# mux_board_final_gp.net
KiCad netlist of a schematic drawn in EAGLE
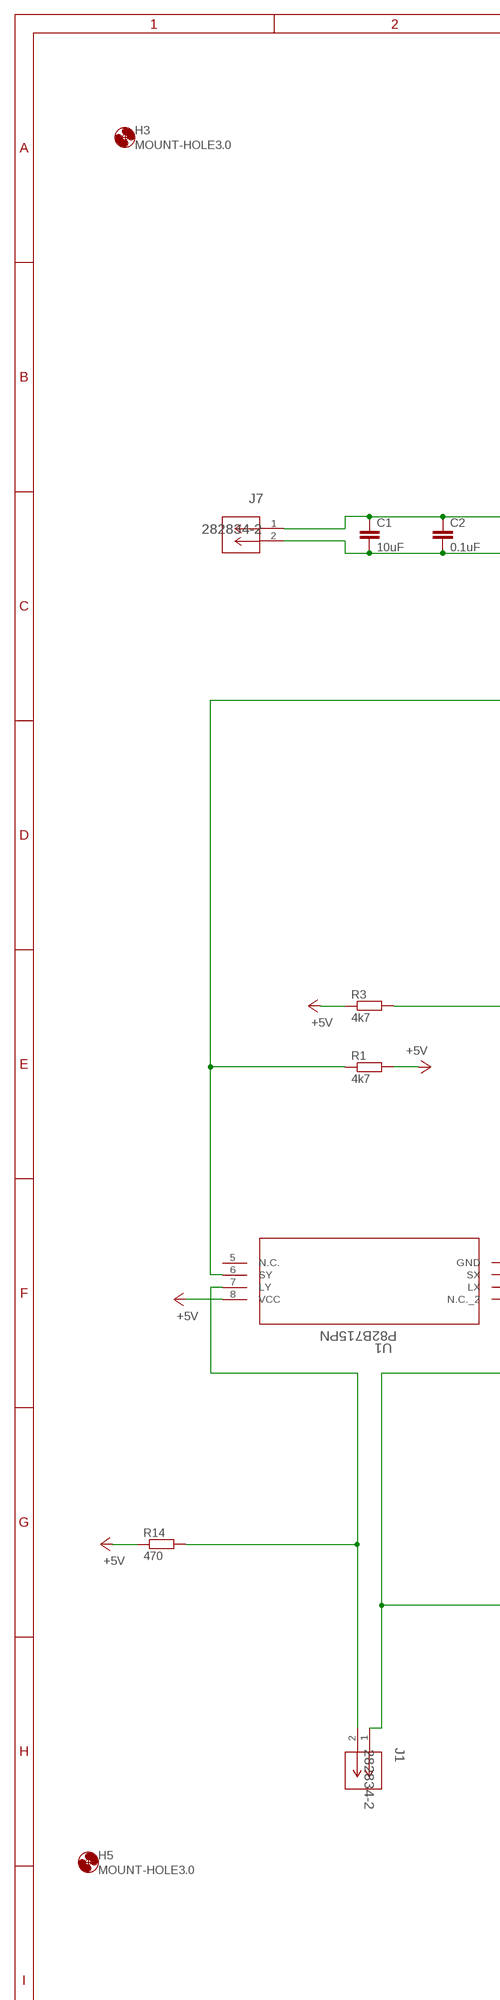
[diagram p0: schematic, sheet 1, part 1 of 2]
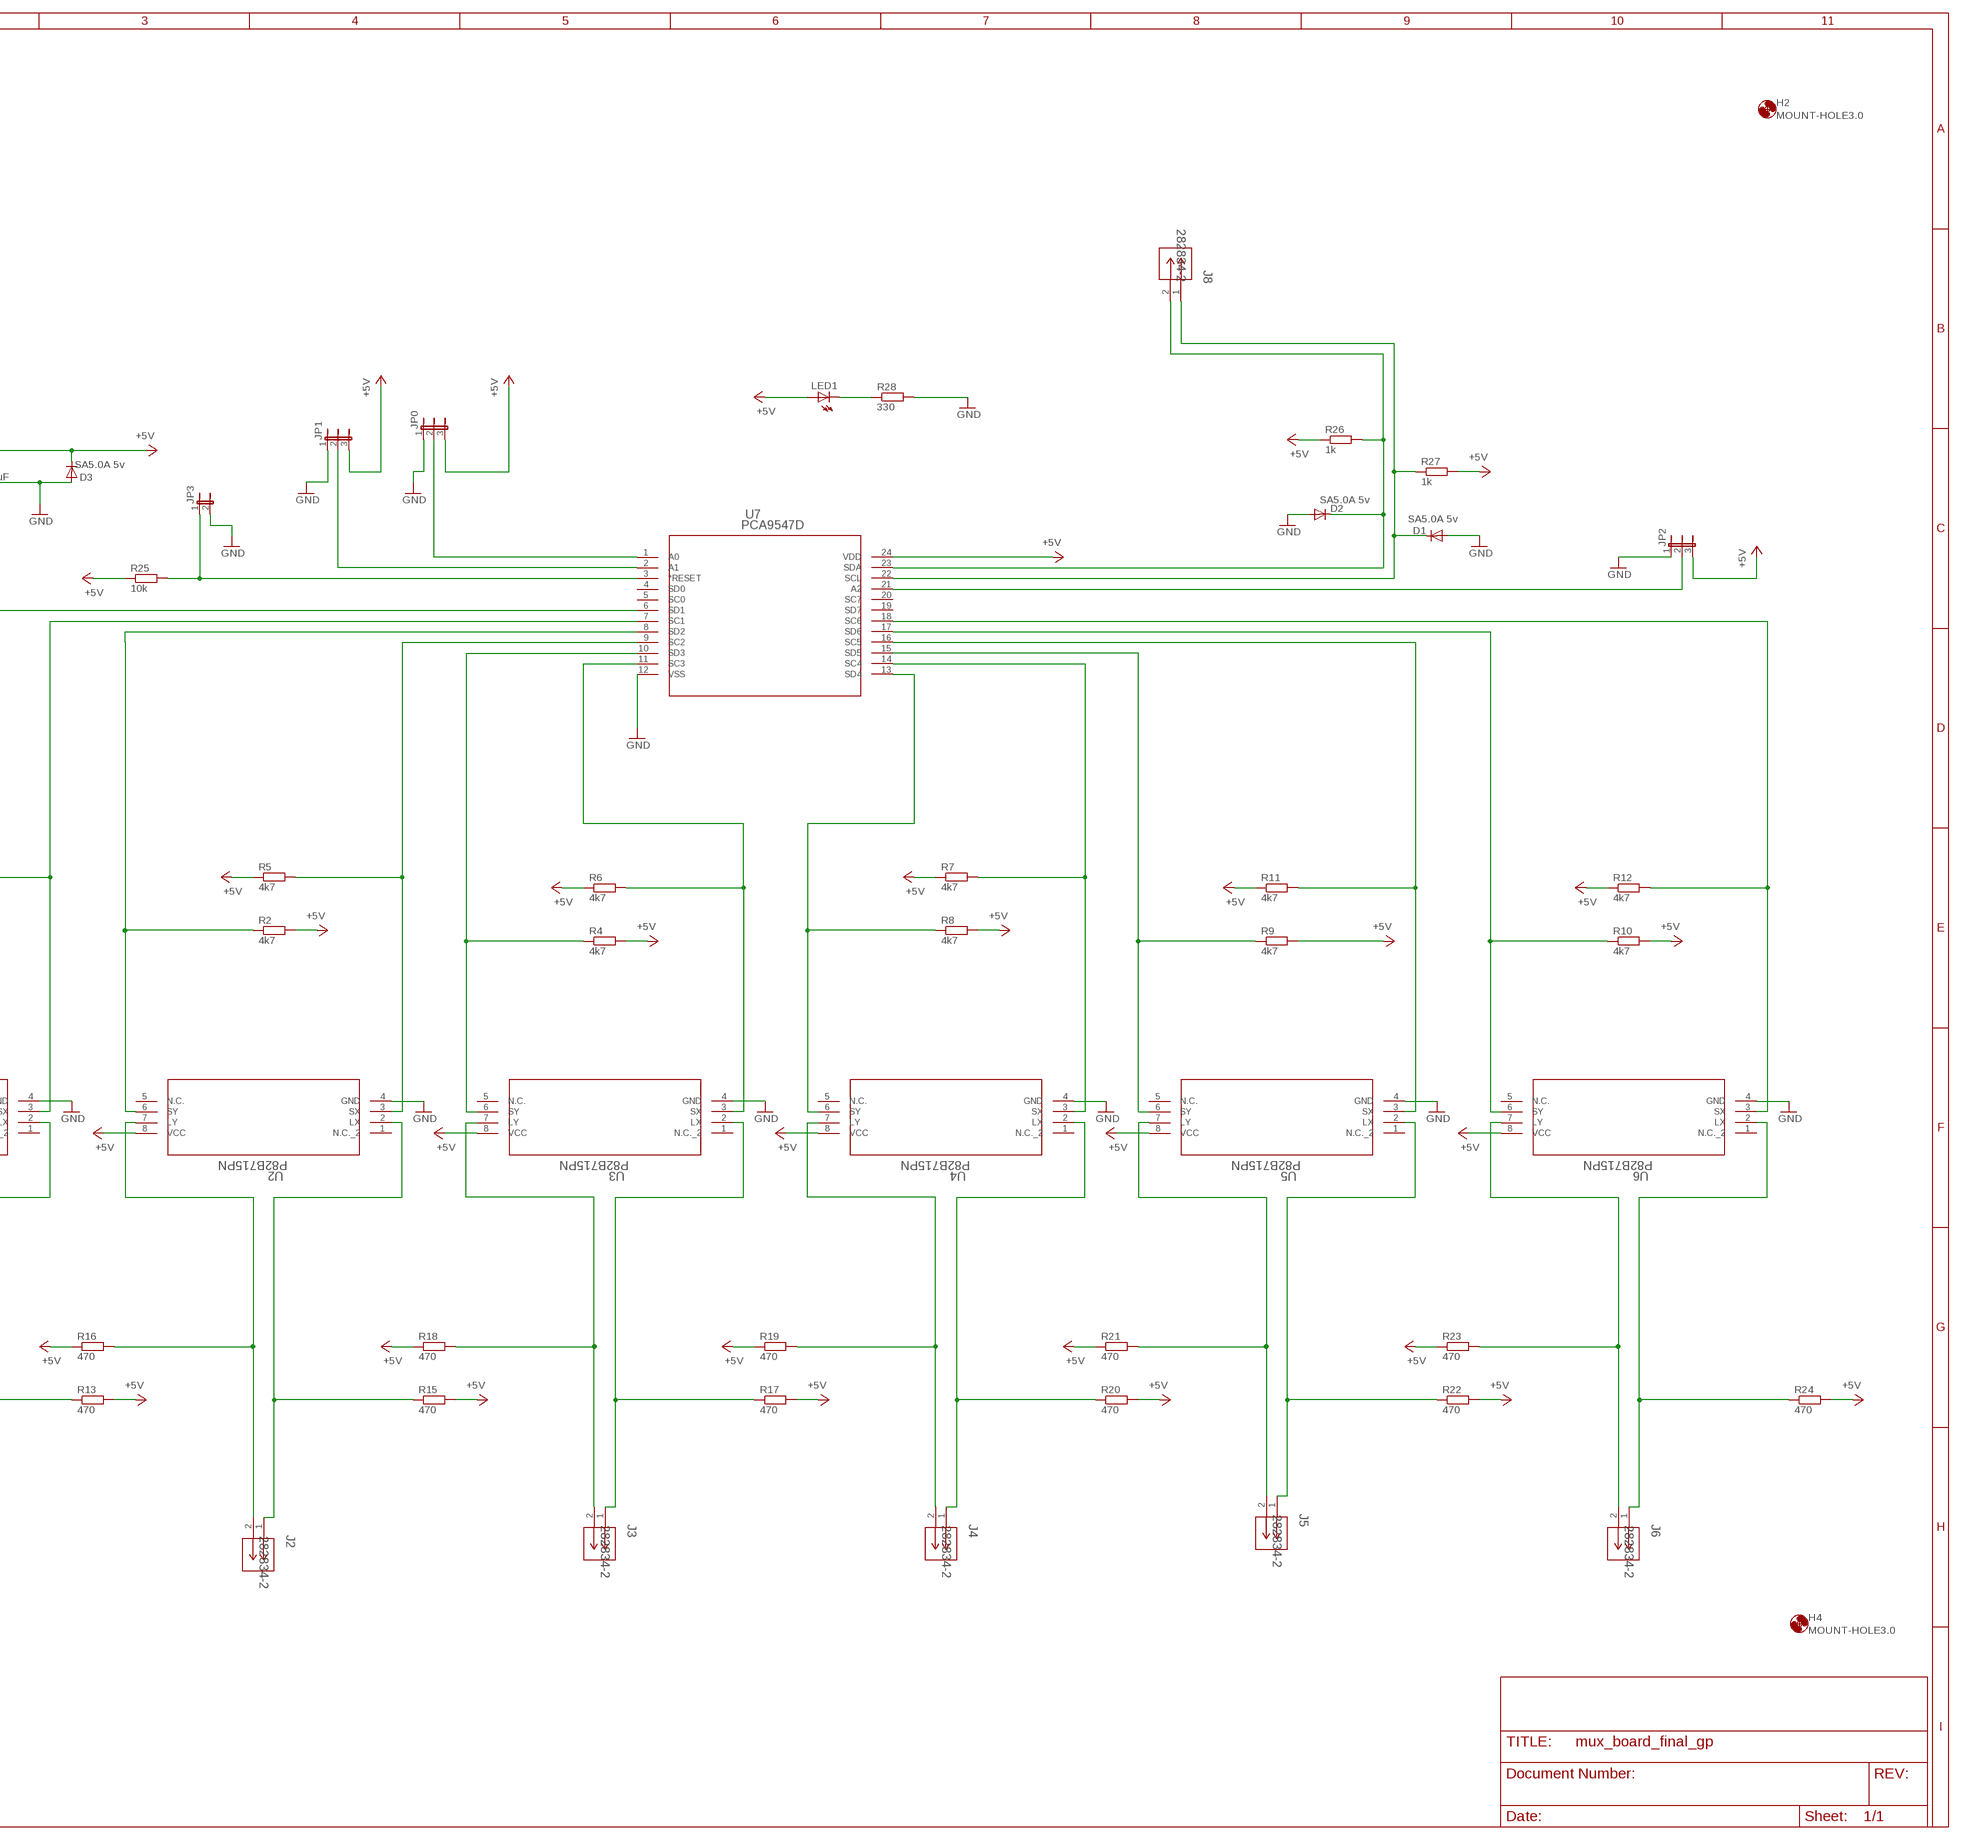
[diagram p1: schematic, sheet 1, part 2 of 2]

(export (version "E")
  (design (tool "Eeschema 10.0.6"))
  (components
    (comp (ref "C1")
      (value "10uF")
      (footprint "eagle-import:C025-025X050")
      (libsource (lib "eagle-import") (part "C-EU025-025X050"))
    )
    (comp (ref "C2")
      (value "0.1uF")
      (footprint "eagle-import:C025-025X050")
      (libsource (lib "eagle-import") (part "C-EU025-025X050"))
    )
    (comp (ref "D1")
      (value "SA5.0A 5v")
      (footprint "eagle-import:DO41-10")
      (libsource (lib "eagle-import") (part "1N4004"))
    )
    (comp (ref "D2")
      (value "SA5.0A 5v")
      (footprint "eagle-import:DO41-10")
      (libsource (lib "eagle-import") (part "1N4004"))
    )
    (comp (ref "D3")
      (value "SA5.0A 5v")
      (footprint "eagle-import:DO41-10")
      (libsource (lib "eagle-import") (part "1N4004"))
    )
    (comp (ref "H2")
      (value "MOUNT-HOLE3.0")
      (footprint "eagle-import:3,0")
      (libsource (lib "eagle-import") (part "MOUNT-HOLE3.0"))
    )
    (comp (ref "H3")
      (value "MOUNT-HOLE3.0")
      (footprint "eagle-import:3,0")
      (libsource (lib "eagle-import") (part "MOUNT-HOLE3.0"))
    )
    (comp (ref "H4")
      (value "MOUNT-HOLE3.0")
      (footprint "eagle-import:3,0")
      (libsource (lib "eagle-import") (part "MOUNT-HOLE3.0"))
    )
    (comp (ref "H5")
      (value "MOUNT-HOLE3.0")
      (footprint "eagle-import:3,0")
      (libsource (lib "eagle-import") (part "MOUNT-HOLE3.0"))
    )
    (comp (ref "J1")
      (value "282834-2")
      (footprint "eagle-import:CONN_282834-2")
      (fields (field (name "RSPARTNUMBER") "7100104"))
      (libsource (lib "eagle-import") (part "282834-2"))
    )
    (comp (ref "J2")
      (value "282834-2")
      (footprint "eagle-import:CONN_282834-2")
      (fields (field (name "RSPARTNUMBER") "7100104"))
      (libsource (lib "eagle-import") (part "282834-2"))
    )
    (comp (ref "J3")
      (value "282834-2")
      (footprint "eagle-import:CONN_282834-2")
      (fields (field (name "RSPARTNUMBER") "7100104"))
      (libsource (lib "eagle-import") (part "282834-2"))
    )
    (comp (ref "J4")
      (value "282834-2")
      (footprint "eagle-import:CONN_282834-2")
      (fields (field (name "RSPARTNUMBER") "7100104"))
      (libsource (lib "eagle-import") (part "282834-2"))
    )
    (comp (ref "J5")
      (value "282834-2")
      (footprint "eagle-import:CONN_282834-2")
      (fields (field (name "RSPARTNUMBER") "7100104"))
      (libsource (lib "eagle-import") (part "282834-2"))
    )
    (comp (ref "J6")
      (value "282834-2")
      (footprint "eagle-import:CONN_282834-2")
      (fields (field (name "RSPARTNUMBER") "7100104"))
      (libsource (lib "eagle-import") (part "282834-2"))
    )
    (comp (ref "J7")
      (value "282834-2")
      (footprint "eagle-import:CONN_282834-2")
      (fields (field (name "RSPARTNUMBER") "7100104"))
      (libsource (lib "eagle-import") (part "282834-2"))
    )
    (comp (ref "J8")
      (value "282834-2")
      (footprint "eagle-import:CONN_282834-2")
      (fields (field (name "RSPARTNUMBER") "7100104"))
      (libsource (lib "eagle-import") (part "282834-2"))
    )
    (comp (ref "JP0")
      (value "JP2E")
      (footprint "eagle-import:JP2")
      (libsource (lib "eagle-import") (part "JP2E"))
    )
    (comp (ref "JP1")
      (value "JP2E")
      (footprint "eagle-import:JP2")
      (libsource (lib "eagle-import") (part "JP2E"))
    )
    (comp (ref "JP2")
      (value "JP2E")
      (footprint "eagle-import:JP2")
      (libsource (lib "eagle-import") (part "JP2E"))
    )
    (comp (ref "JP3")
      (value "JP1E")
      (footprint "eagle-import:JP1")
      (libsource (lib "eagle-import") (part "JP1E"))
    )
    (comp (ref "LED1")
      (value "LED3MM")
      (footprint "eagle-import:LED3MM")
      (libsource (lib "eagle-import") (part "LED3MM"))
    )
    (comp (ref "R1")
      (value "4k7")
      (footprint "eagle-import:0204_7")
      (libsource (lib "eagle-import") (part "R-EU_0204/7"))
    )
    (comp (ref "R2")
      (value "4k7")
      (footprint "eagle-import:0204_7")
      (libsource (lib "eagle-import") (part "R-EU_0204/7"))
    )
    (comp (ref "R3")
      (value "4k7")
      (footprint "eagle-import:0204_7")
      (libsource (lib "eagle-import") (part "R-EU_0204/7"))
    )
    (comp (ref "R4")
      (value "4k7")
      (footprint "eagle-import:0204_7")
      (libsource (lib "eagle-import") (part "R-EU_0204/7"))
    )
    (comp (ref "R5")
      (value "4k7")
      (footprint "eagle-import:0204_7")
      (libsource (lib "eagle-import") (part "R-EU_0204/7"))
    )
    (comp (ref "R6")
      (value "4k7")
      (footprint "eagle-import:0204_7")
      (libsource (lib "eagle-import") (part "R-EU_0204/7"))
    )
    (comp (ref "R7")
      (value "4k7")
      (footprint "eagle-import:0204_7")
      (libsource (lib "eagle-import") (part "R-EU_0204/7"))
    )
    (comp (ref "R8")
      (value "4k7")
      (footprint "eagle-import:0204_7")
      (libsource (lib "eagle-import") (part "R-EU_0204/7"))
    )
    (comp (ref "R9")
      (value "4k7")
      (footprint "eagle-import:0204_7")
      (libsource (lib "eagle-import") (part "R-EU_0204/7"))
    )
    (comp (ref "R10")
      (value "4k7")
      (footprint "eagle-import:0204_7")
      (libsource (lib "eagle-import") (part "R-EU_0204/7"))
    )
    (comp (ref "R11")
      (value "4k7")
      (footprint "eagle-import:0204_7")
      (libsource (lib "eagle-import") (part "R-EU_0204/7"))
    )
    (comp (ref "R12")
      (value "4k7")
      (footprint "eagle-import:0204_7")
      (libsource (lib "eagle-import") (part "R-EU_0204/7"))
    )
    (comp (ref "R13")
      (value "470")
      (footprint "eagle-import:0204_7")
      (libsource (lib "eagle-import") (part "R-EU_0204/7"))
    )
    (comp (ref "R14")
      (value "470")
      (footprint "eagle-import:0204_7")
      (libsource (lib "eagle-import") (part "R-EU_0204/7"))
    )
    (comp (ref "R15")
      (value "470")
      (footprint "eagle-import:0204_7")
      (libsource (lib "eagle-import") (part "R-EU_0204/7"))
    )
    (comp (ref "R16")
      (value "470")
      (footprint "eagle-import:0204_7")
      (libsource (lib "eagle-import") (part "R-EU_0204/7"))
    )
    (comp (ref "R17")
      (value "470")
      (footprint "eagle-import:0204_7")
      (libsource (lib "eagle-import") (part "R-EU_0204/7"))
    )
    (comp (ref "R18")
      (value "470")
      (footprint "eagle-import:0204_7")
      (libsource (lib "eagle-import") (part "R-EU_0204/7"))
    )
    (comp (ref "R19")
      (value "470")
      (footprint "eagle-import:0204_7")
      (libsource (lib "eagle-import") (part "R-EU_0204/7"))
    )
    (comp (ref "R20")
      (value "470")
      (footprint "eagle-import:0204_7")
      (libsource (lib "eagle-import") (part "R-EU_0204/7"))
    )
    (comp (ref "R21")
      (value "470")
      (footprint "eagle-import:0204_7")
      (libsource (lib "eagle-import") (part "R-EU_0204/7"))
    )
    (comp (ref "R22")
      (value "470")
      (footprint "eagle-import:0204_7")
      (libsource (lib "eagle-import") (part "R-EU_0204/7"))
    )
    (comp (ref "R23")
      (value "470")
      (footprint "eagle-import:0204_7")
      (libsource (lib "eagle-import") (part "R-EU_0204/7"))
    )
    (comp (ref "R24")
      (value "470")
      (footprint "eagle-import:0204_7")
      (libsource (lib "eagle-import") (part "R-EU_0204/7"))
    )
    (comp (ref "R25")
      (value "10k")
      (footprint "eagle-import:0204_7")
      (libsource (lib "eagle-import") (part "R-EU_0204/7"))
    )
    (comp (ref "R26")
      (value "1k")
      (footprint "eagle-import:0204_7")
      (libsource (lib "eagle-import") (part "R-EU_0204/7"))
    )
    (comp (ref "R27")
      (value "1k")
      (footprint "eagle-import:0204_7")
      (libsource (lib "eagle-import") (part "R-EU_0204/7"))
    )
    (comp (ref "R28")
      (value "330")
      (footprint "eagle-import:0204_7")
      (libsource (lib "eagle-import") (part "R-EU_0204/7"))
    )
    (comp (ref "U1")
      (value "P82B715PN")
      (footprint "eagle-import:SOT97-1")
      (fields (field (name "RSPARTNUMBER") "821784"))
      (libsource (lib "eagle-import") (part "P82B715PN"))
    )
    (comp (ref "U2")
      (value "P82B715PN")
      (footprint "eagle-import:SOT97-1")
      (fields (field (name "RSPARTNUMBER") "821784"))
      (libsource (lib "eagle-import") (part "P82B715PN"))
    )
    (comp (ref "U3")
      (value "P82B715PN")
      (footprint "eagle-import:SOT97-1")
      (fields (field (name "RSPARTNUMBER") "821784"))
      (libsource (lib "eagle-import") (part "P82B715PN"))
    )
    (comp (ref "U4")
      (value "P82B715PN")
      (footprint "eagle-import:SOT97-1")
      (fields (field (name "RSPARTNUMBER") "821784"))
      (libsource (lib "eagle-import") (part "P82B715PN"))
    )
    (comp (ref "U5")
      (value "P82B715PN")
      (footprint "eagle-import:SOT97-1")
      (fields (field (name "RSPARTNUMBER") "821784"))
      (libsource (lib "eagle-import") (part "P82B715PN"))
    )
    (comp (ref "U6")
      (value "P82B715PN")
      (footprint "eagle-import:SOT97-1")
      (fields (field (name "RSPARTNUMBER") "821784"))
      (libsource (lib "eagle-import") (part "P82B715PN"))
    )
    (comp (ref "U7")
      (value "PCA9547D")
      (footprint "eagle-import:SOT137-1")
      (fields (field (name "RSPARTNUMBER") "7258877"))
      (libsource (lib "eagle-import") (part "PCA9547D"))
    )
  )
  (nets
    (net (code "1") (name "+5V") (class "Default")
      (node (ref "C1") (pin "1") (pinfunction "1_1") (pintype "passive"))
      (node (ref "C2") (pin "1") (pinfunction "1_1") (pintype "passive"))
      (node (ref "D3") (pin "C") (pinfunction "C_C") (pintype "passive"))
      (node (ref "J7") (pin "1") (pinfunction "1_1") (pintype "passive"))
      (node (ref "JP0") (pin "3") (pinfunction "3_3") (pintype "passive"))
      (node (ref "JP1") (pin "3") (pinfunction "3_3") (pintype "passive"))
      (node (ref "JP2") (pin "3") (pinfunction "3_3") (pintype "passive"))
      (node (ref "LED1") (pin "A") (pinfunction "A_A") (pintype "passive"))
      (node (ref "R1") (pin "2") (pinfunction "2_2") (pintype "passive"))
      (node (ref "R10") (pin "2") (pinfunction "2_2") (pintype "passive"))
      (node (ref "R11") (pin "1") (pinfunction "1_1") (pintype "passive"))
      (node (ref "R12") (pin "1") (pinfunction "1_1") (pintype "passive"))
      (node (ref "R13") (pin "2") (pinfunction "2_2") (pintype "passive"))
      (node (ref "R14") (pin "1") (pinfunction "1_1") (pintype "passive"))
      (node (ref "R15") (pin "2") (pinfunction "2_2") (pintype "passive"))
      (node (ref "R16") (pin "1") (pinfunction "1_1") (pintype "passive"))
      (node (ref "R17") (pin "2") (pinfunction "2_2") (pintype "passive"))
      (node (ref "R18") (pin "1") (pinfunction "1_1") (pintype "passive"))
      (node (ref "R19") (pin "1") (pinfunction "1_1") (pintype "passive"))
      (node (ref "R2") (pin "2") (pinfunction "2_2") (pintype "passive"))
      (node (ref "R20") (pin "2") (pinfunction "2_2") (pintype "passive"))
      (node (ref "R21") (pin "1") (pinfunction "1_1") (pintype "passive"))
      (node (ref "R22") (pin "2") (pinfunction "2_2") (pintype "passive"))
      (node (ref "R23") (pin "1") (pinfunction "1_1") (pintype "passive"))
      (node (ref "R24") (pin "2") (pinfunction "2_2") (pintype "passive"))
      (node (ref "R25") (pin "1") (pinfunction "1_1") (pintype "passive"))
      (node (ref "R26") (pin "1") (pinfunction "1_1") (pintype "passive"))
      (node (ref "R27") (pin "2") (pinfunction "2_2") (pintype "passive"))
      (node (ref "R3") (pin "1") (pinfunction "1_1") (pintype "passive"))
      (node (ref "R4") (pin "2") (pinfunction "2_2") (pintype "passive"))
      (node (ref "R5") (pin "1") (pinfunction "1_1") (pintype "passive"))
      (node (ref "R6") (pin "1") (pinfunction "1_1") (pintype "passive"))
      (node (ref "R7") (pin "1") (pinfunction "1_1") (pintype "passive"))
      (node (ref "R8") (pin "2") (pinfunction "2_2") (pintype "passive"))
      (node (ref "R9") (pin "2") (pinfunction "2_2") (pintype "passive"))
      (node (ref "U1") (pin "8") (pinfunction "VCC_8") (pintype "passive"))
      (node (ref "U2") (pin "8") (pinfunction "VCC_8") (pintype "passive"))
      (node (ref "U3") (pin "8") (pinfunction "VCC_8") (pintype "passive"))
      (node (ref "U4") (pin "8") (pinfunction "VCC_8") (pintype "passive"))
      (node (ref "U5") (pin "8") (pinfunction "VCC_8") (pintype "passive"))
      (node (ref "U6") (pin "8") (pinfunction "VCC_8") (pintype "passive"))
      (node (ref "U7") (pin "24") (pinfunction "VDD_24") (pintype "passive"))
    )
    (net (code "2") (name "GND") (class "Default")
      (node (ref "C1") (pin "2") (pinfunction "2_2") (pintype "passive"))
      (node (ref "C2") (pin "2") (pinfunction "2_2") (pintype "passive"))
      (node (ref "D1") (pin "A") (pinfunction "A_A") (pintype "passive"))
      (node (ref "D2") (pin "A") (pinfunction "A_A") (pintype "passive"))
      (node (ref "D3") (pin "A") (pinfunction "A_A") (pintype "passive"))
      (node (ref "J7") (pin "2") (pinfunction "2_2") (pintype "passive"))
      (node (ref "JP0") (pin "1") (pinfunction "1_1") (pintype "passive"))
      (node (ref "JP1") (pin "1") (pinfunction "1_1") (pintype "passive"))
      (node (ref "JP2") (pin "1") (pinfunction "1_1") (pintype "passive"))
      (node (ref "JP3") (pin "2") (pinfunction "2_2") (pintype "passive"))
      (node (ref "R28") (pin "2") (pinfunction "2_2") (pintype "passive"))
      (node (ref "U1") (pin "4") (pinfunction "GND_4") (pintype "passive"))
      (node (ref "U2") (pin "4") (pinfunction "GND_4") (pintype "passive"))
      (node (ref "U3") (pin "4") (pinfunction "GND_4") (pintype "passive"))
      (node (ref "U4") (pin "4") (pinfunction "GND_4") (pintype "passive"))
      (node (ref "U5") (pin "4") (pinfunction "GND_4") (pintype "passive"))
      (node (ref "U6") (pin "4") (pinfunction "GND_4") (pintype "passive"))
      (node (ref "U7") (pin "12") (pinfunction "VSS_12") (pintype "passive"))
    )
    (net (code "3") (name "Net-(LED1-C)") (class "Default")
      (node (ref "LED1") (pin "K") (pinfunction "C_K") (pintype "passive"))
      (node (ref "R28") (pin "1") (pinfunction "1_1") (pintype "passive"))
    )
    (net (code "4") (name "Net-(U1-LX)") (class "Default")
      (node (ref "J1") (pin "1") (pinfunction "1_1") (pintype "passive"))
      (node (ref "R13") (pin "1") (pinfunction "1_1") (pintype "passive"))
      (node (ref "U1") (pin "2") (pinfunction "LX_2") (pintype "passive"))
    )
    (net (code "5") (name "Net-(U1-LY)") (class "Default")
      (node (ref "J1") (pin "2") (pinfunction "2_2") (pintype "passive"))
      (node (ref "R14") (pin "2") (pinfunction "2_2") (pintype "passive"))
      (node (ref "U1") (pin "7") (pinfunction "LY_7") (pintype "passive"))
    )
    (net (code "6") (name "Net-(U1-SX)") (class "Default")
      (node (ref "R3") (pin "2") (pinfunction "2_2") (pintype "passive"))
      (node (ref "U1") (pin "3") (pinfunction "SX_3") (pintype "passive"))
      (node (ref "U7") (pin "7") (pinfunction "SC1_7") (pintype "passive"))
    )
    (net (code "7") (name "Net-(U1-SY)") (class "Default")
      (node (ref "R1") (pin "1") (pinfunction "1_1") (pintype "passive"))
      (node (ref "U1") (pin "6") (pinfunction "SY_6") (pintype "passive"))
      (node (ref "U7") (pin "6") (pinfunction "SD1_6") (pintype "passive"))
    )
    (net (code "8") (name "Net-(U2-LX)") (class "Default")
      (node (ref "J2") (pin "1") (pinfunction "1_1") (pintype "passive"))
      (node (ref "R15") (pin "1") (pinfunction "1_1") (pintype "passive"))
      (node (ref "U2") (pin "2") (pinfunction "LX_2") (pintype "passive"))
    )
    (net (code "9") (name "Net-(U2-LY)") (class "Default")
      (node (ref "J2") (pin "2") (pinfunction "2_2") (pintype "passive"))
      (node (ref "R16") (pin "2") (pinfunction "2_2") (pintype "passive"))
      (node (ref "U2") (pin "7") (pinfunction "LY_7") (pintype "passive"))
    )
    (net (code "10") (name "Net-(U2-SX)") (class "Default")
      (node (ref "R5") (pin "2") (pinfunction "2_2") (pintype "passive"))
      (node (ref "U2") (pin "3") (pinfunction "SX_3") (pintype "passive"))
      (node (ref "U7") (pin "9") (pinfunction "SC2_9") (pintype "passive"))
    )
    (net (code "11") (name "Net-(U2-SY)") (class "Default")
      (node (ref "R2") (pin "1") (pinfunction "1_1") (pintype "passive"))
      (node (ref "U2") (pin "6") (pinfunction "SY_6") (pintype "passive"))
      (node (ref "U7") (pin "8") (pinfunction "SD2_8") (pintype "passive"))
    )
    (net (code "12") (name "Net-(U3-LX)") (class "Default")
      (node (ref "J3") (pin "1") (pinfunction "1_1") (pintype "passive"))
      (node (ref "R17") (pin "1") (pinfunction "1_1") (pintype "passive"))
      (node (ref "U3") (pin "2") (pinfunction "LX_2") (pintype "passive"))
    )
    (net (code "13") (name "Net-(U3-LY)") (class "Default")
      (node (ref "J3") (pin "2") (pinfunction "2_2") (pintype "passive"))
      (node (ref "R18") (pin "2") (pinfunction "2_2") (pintype "passive"))
      (node (ref "U3") (pin "7") (pinfunction "LY_7") (pintype "passive"))
    )
    (net (code "14") (name "Net-(U3-SX)") (class "Default")
      (node (ref "R6") (pin "2") (pinfunction "2_2") (pintype "passive"))
      (node (ref "U3") (pin "3") (pinfunction "SX_3") (pintype "passive"))
      (node (ref "U7") (pin "11") (pinfunction "SC3_11") (pintype "passive"))
    )
    (net (code "15") (name "Net-(U3-SY)") (class "Default")
      (node (ref "R4") (pin "1") (pinfunction "1_1") (pintype "passive"))
      (node (ref "U3") (pin "6") (pinfunction "SY_6") (pintype "passive"))
      (node (ref "U7") (pin "10") (pinfunction "SD3_10") (pintype "passive"))
    )
    (net (code "16") (name "Net-(U4-LX)") (class "Default")
      (node (ref "J4") (pin "1") (pinfunction "1_1") (pintype "passive"))
      (node (ref "R20") (pin "1") (pinfunction "1_1") (pintype "passive"))
      (node (ref "U4") (pin "2") (pinfunction "LX_2") (pintype "passive"))
    )
    (net (code "17") (name "Net-(U4-LY)") (class "Default")
      (node (ref "J4") (pin "2") (pinfunction "2_2") (pintype "passive"))
      (node (ref "R19") (pin "2") (pinfunction "2_2") (pintype "passive"))
      (node (ref "U4") (pin "7") (pinfunction "LY_7") (pintype "passive"))
    )
    (net (code "18") (name "Net-(U4-SX)") (class "Default")
      (node (ref "R7") (pin "2") (pinfunction "2_2") (pintype "passive"))
      (node (ref "U4") (pin "3") (pinfunction "SX_3") (pintype "passive"))
      (node (ref "U7") (pin "14") (pinfunction "SC4_14") (pintype "passive"))
    )
    (net (code "19") (name "Net-(U4-SY)") (class "Default")
      (node (ref "R8") (pin "1") (pinfunction "1_1") (pintype "passive"))
      (node (ref "U4") (pin "6") (pinfunction "SY_6") (pintype "passive"))
      (node (ref "U7") (pin "13") (pinfunction "SD4_13") (pintype "passive"))
    )
    (net (code "20") (name "Net-(U5-LX)") (class "Default")
      (node (ref "J5") (pin "1") (pinfunction "1_1") (pintype "passive"))
      (node (ref "R22") (pin "1") (pinfunction "1_1") (pintype "passive"))
      (node (ref "U5") (pin "2") (pinfunction "LX_2") (pintype "passive"))
    )
    (net (code "21") (name "Net-(U5-LY)") (class "Default")
      (node (ref "J5") (pin "2") (pinfunction "2_2") (pintype "passive"))
      (node (ref "R21") (pin "2") (pinfunction "2_2") (pintype "passive"))
      (node (ref "U5") (pin "7") (pinfunction "LY_7") (pintype "passive"))
    )
    (net (code "22") (name "Net-(U5-SX)") (class "Default")
      (node (ref "R11") (pin "2") (pinfunction "2_2") (pintype "passive"))
      (node (ref "U5") (pin "3") (pinfunction "SX_3") (pintype "passive"))
      (node (ref "U7") (pin "16") (pinfunction "SC5_16") (pintype "passive"))
    )
    (net (code "23") (name "Net-(U5-SY)") (class "Default")
      (node (ref "R9") (pin "1") (pinfunction "1_1") (pintype "passive"))
      (node (ref "U5") (pin "6") (pinfunction "SY_6") (pintype "passive"))
      (node (ref "U7") (pin "15") (pinfunction "SD5_15") (pintype "passive"))
    )
    (net (code "24") (name "Net-(U6-LX)") (class "Default")
      (node (ref "J6") (pin "1") (pinfunction "1_1") (pintype "passive"))
      (node (ref "R24") (pin "1") (pinfunction "1_1") (pintype "passive"))
      (node (ref "U6") (pin "2") (pinfunction "LX_2") (pintype "passive"))
    )
    (net (code "25") (name "Net-(U6-LY)") (class "Default")
      (node (ref "J6") (pin "2") (pinfunction "2_2") (pintype "passive"))
      (node (ref "R23") (pin "2") (pinfunction "2_2") (pintype "passive"))
      (node (ref "U6") (pin "7") (pinfunction "LY_7") (pintype "passive"))
    )
    (net (code "26") (name "Net-(U6-SX)") (class "Default")
      (node (ref "R12") (pin "2") (pinfunction "2_2") (pintype "passive"))
      (node (ref "U6") (pin "3") (pinfunction "SX_3") (pintype "passive"))
      (node (ref "U7") (pin "18") (pinfunction "SC6_18") (pintype "passive"))
    )
    (net (code "27") (name "Net-(U6-SY)") (class "Default")
      (node (ref "R10") (pin "1") (pinfunction "1_1") (pintype "passive"))
      (node (ref "U6") (pin "6") (pinfunction "SY_6") (pintype "passive"))
      (node (ref "U7") (pin "17") (pinfunction "SD6_17") (pintype "passive"))
    )
    (net (code "28") (name "Net-(U7-*RESET)") (class "Default")
      (node (ref "JP3") (pin "1") (pinfunction "1_1") (pintype "passive"))
      (node (ref "R25") (pin "2") (pinfunction "2_2") (pintype "passive"))
      (node (ref "U7") (pin "3") (pinfunction "*RESET_3") (pintype "passive"))
    )
    (net (code "29") (name "Net-(U7-A0)") (class "Default")
      (node (ref "JP0") (pin "2") (pinfunction "2_2") (pintype "passive"))
      (node (ref "U7") (pin "1") (pinfunction "A0_1") (pintype "passive"))
    )
    (net (code "30") (name "Net-(U7-A1)") (class "Default")
      (node (ref "JP1") (pin "2") (pinfunction "2_2") (pintype "passive"))
      (node (ref "U7") (pin "2") (pinfunction "A1_2") (pintype "passive"))
    )
    (net (code "31") (name "Net-(U7-A2)") (class "Default")
      (node (ref "JP2") (pin "2") (pinfunction "2_2") (pintype "passive"))
      (node (ref "U7") (pin "21") (pinfunction "A2_21") (pintype "passive"))
    )
    (net (code "32") (name "Net-(U7-SCL)") (class "Default")
      (node (ref "D1") (pin "C") (pinfunction "C_C") (pintype "passive"))
      (node (ref "J8") (pin "1") (pinfunction "1_1") (pintype "passive"))
      (node (ref "R27") (pin "1") (pinfunction "1_1") (pintype "passive"))
      (node (ref "U7") (pin "22") (pinfunction "SCL_22") (pintype "passive"))
    )
    (net (code "33") (name "Net-(U7-SDA)") (class "Default")
      (node (ref "D2") (pin "C") (pinfunction "C_C") (pintype "passive"))
      (node (ref "J8") (pin "2") (pinfunction "2_2") (pintype "passive"))
      (node (ref "R26") (pin "2") (pinfunction "2_2") (pintype "passive"))
      (node (ref "U7") (pin "23") (pinfunction "SDA_23") (pintype "passive"))
    )
    (net (code "34") (name "unconnected-(U1-N.C.-Pad5)") (class "Default")
      (node (ref "U1") (pin "5") (pinfunction "N.C._5") (pintype "passive"))
    )
    (net (code "35") (name "unconnected-(U1-N.C._2-Pad1)") (class "Default")
      (node (ref "U1") (pin "1") (pinfunction "N.C._2_1") (pintype "passive"))
    )
    (net (code "36") (name "unconnected-(U2-N.C.-Pad5)") (class "Default")
      (node (ref "U2") (pin "5") (pinfunction "N.C._5") (pintype "passive"))
    )
    (net (code "37") (name "unconnected-(U2-N.C._2-Pad1)") (class "Default")
      (node (ref "U2") (pin "1") (pinfunction "N.C._2_1") (pintype "passive"))
    )
    (net (code "38") (name "unconnected-(U3-N.C.-Pad5)") (class "Default")
      (node (ref "U3") (pin "5") (pinfunction "N.C._5") (pintype "passive"))
    )
    (net (code "39") (name "unconnected-(U3-N.C._2-Pad1)") (class "Default")
      (node (ref "U3") (pin "1") (pinfunction "N.C._2_1") (pintype "passive"))
    )
    (net (code "40") (name "unconnected-(U4-N.C.-Pad5)") (class "Default")
      (node (ref "U4") (pin "5") (pinfunction "N.C._5") (pintype "passive"))
    )
    (net (code "41") (name "unconnected-(U4-N.C._2-Pad1)") (class "Default")
      (node (ref "U4") (pin "1") (pinfunction "N.C._2_1") (pintype "passive"))
    )
    (net (code "42") (name "unconnected-(U5-N.C.-Pad5)") (class "Default")
      (node (ref "U5") (pin "5") (pinfunction "N.C._5") (pintype "passive"))
    )
    (net (code "43") (name "unconnected-(U5-N.C._2-Pad1)") (class "Default")
      (node (ref "U5") (pin "1") (pinfunction "N.C._2_1") (pintype "passive"))
    )
    (net (code "44") (name "unconnected-(U6-N.C.-Pad5)") (class "Default")
      (node (ref "U6") (pin "5") (pinfunction "N.C._5") (pintype "passive"))
    )
    (net (code "45") (name "unconnected-(U6-N.C._2-Pad1)") (class "Default")
      (node (ref "U6") (pin "1") (pinfunction "N.C._2_1") (pintype "passive"))
    )
    (net (code "46") (name "unconnected-(U7-SC0-Pad5)") (class "Default")
      (node (ref "U7") (pin "5") (pinfunction "SC0_5") (pintype "passive"))
    )
    (net (code "47") (name "unconnected-(U7-SC7-Pad20)") (class "Default")
      (node (ref "U7") (pin "20") (pinfunction "SC7_20") (pintype "passive"))
    )
    (net (code "48") (name "unconnected-(U7-SD0-Pad4)") (class "Default")
      (node (ref "U7") (pin "4") (pinfunction "SD0_4") (pintype "passive"))
    )
    (net (code "49") (name "unconnected-(U7-SD7-Pad19)") (class "Default")
      (node (ref "U7") (pin "19") (pinfunction "SD7_19") (pintype "passive"))
    )
  )
)
